# TMS1_2025_INVERTED.net
KiCad netlist of a schematic drawn in EasyEDA
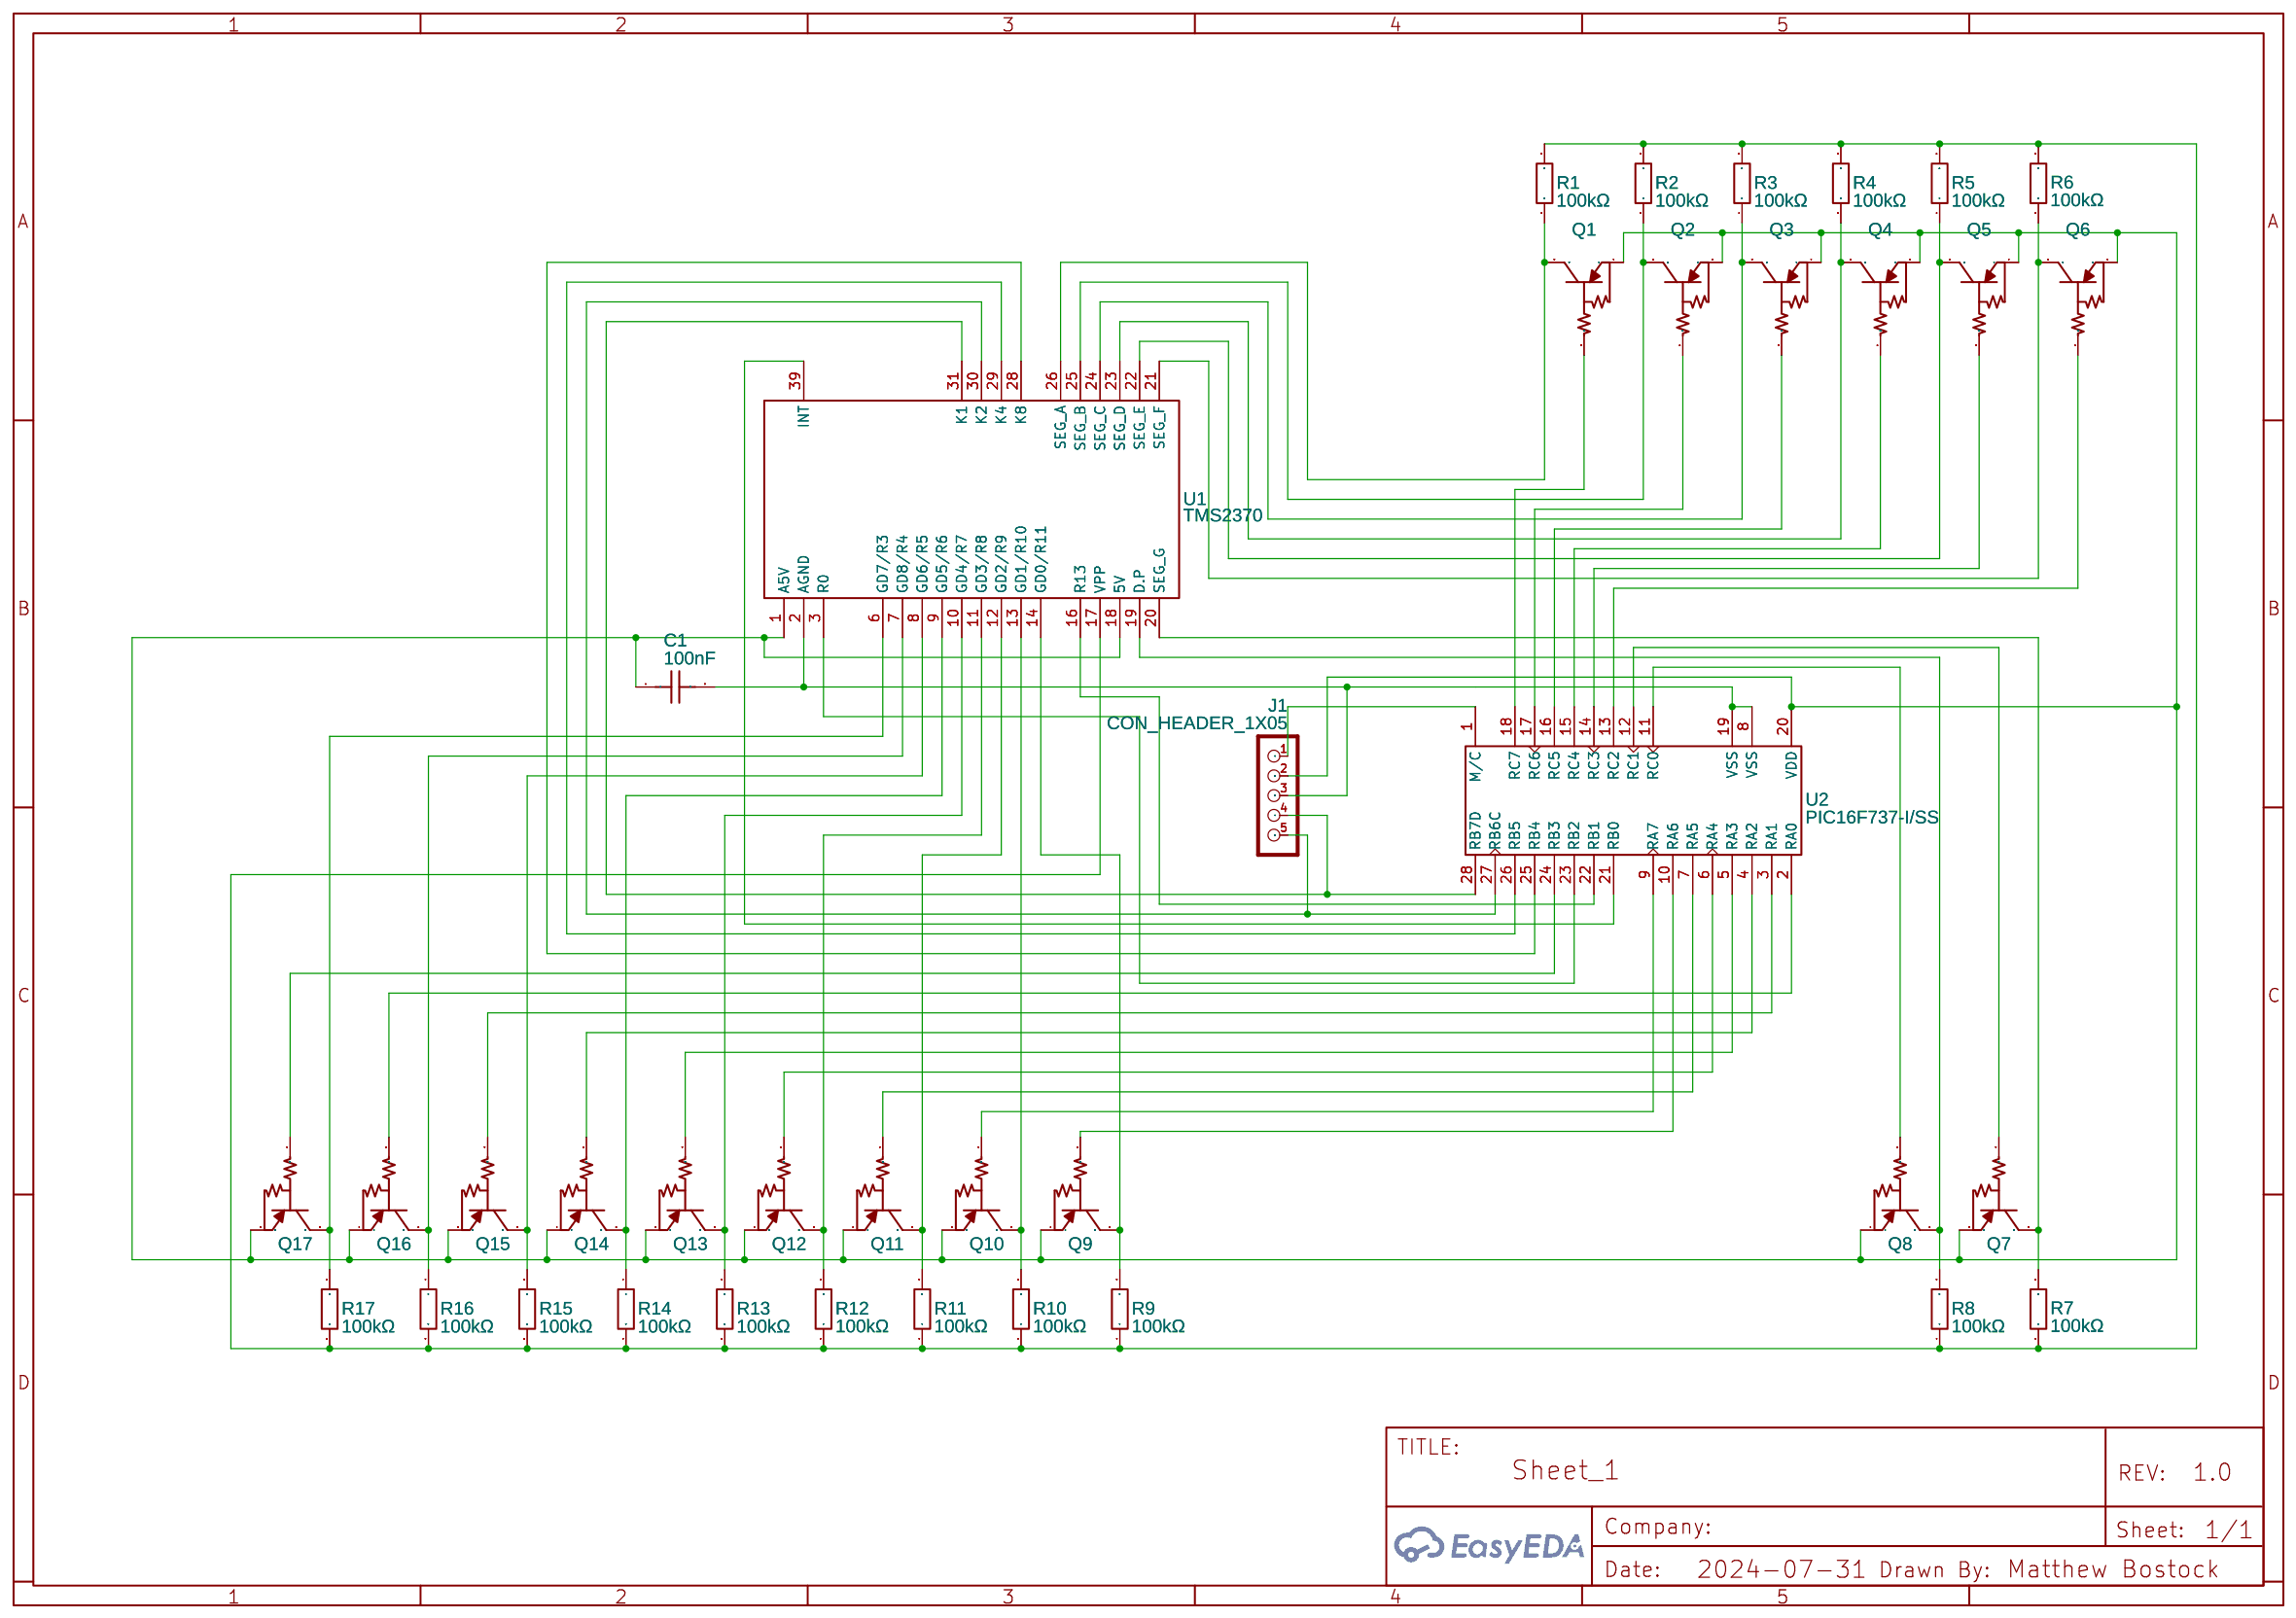
[diagram p0: schematic sheet]

(export (version "E")
  (design (tool "Eeschema 10.0.6"))
  (components
    (comp (ref "C1")
      (value "100nF")
      (fields
        (field (name "Manufacturer Part") "CC0603KRX7R9BB104")
        (field (name "Manufacturer") "YAGEO(国巨)")
      )
      (libsource (lib "") (part "CC0603KRX7R9BB104"))
    )
    (comp (ref "J1") (value "CON_HEADER_1X05") (libsource (lib "") (part "CON_HEADER_1X05")))
    (comp (ref "Q1")
      (value "DTB113ZKT146_SLIM")
      (fields (field (name "Manufacturer Part") "DTB113ZKT146") (field (name "Manufacturer") "ROHM(罗姆)"))
      (libsource (lib "") (part "DTB113ZKT146_SLIM_1"))
    )
    (comp (ref "Q2")
      (value "DTB113ZKT146_SLIM")
      (fields (field (name "Manufacturer Part") "DTB113ZKT146") (field (name "Manufacturer") "ROHM(罗姆)"))
      (libsource (lib "") (part "DTB113ZKT146_SLIM_1"))
    )
    (comp (ref "Q3")
      (value "DTB113ZKT146_SLIM")
      (fields (field (name "Manufacturer Part") "DTB113ZKT146") (field (name "Manufacturer") "ROHM(罗姆)"))
      (libsource (lib "") (part "DTB113ZKT146_SLIM_1"))
    )
    (comp (ref "Q4")
      (value "DTB113ZKT146_SLIM")
      (fields (field (name "Manufacturer Part") "DTB113ZKT146") (field (name "Manufacturer") "ROHM(罗姆)"))
      (libsource (lib "") (part "DTB113ZKT146_SLIM_1"))
    )
    (comp (ref "Q5")
      (value "DTB113ZKT146_SLIM")
      (fields (field (name "Manufacturer Part") "DTB113ZKT146") (field (name "Manufacturer") "ROHM(罗姆)"))
      (libsource (lib "") (part "DTB113ZKT146_SLIM_1"))
    )
    (comp (ref "Q6")
      (value "DTB113ZKT146_SLIM")
      (fields (field (name "Manufacturer Part") "DTB113ZKT146") (field (name "Manufacturer") "ROHM(罗姆)"))
      (libsource (lib "") (part "DTB113ZKT146_SLIM_1"))
    )
    (comp (ref "Q7")
      (value "DTB113ZKT146_SLIM")
      (fields (field (name "Manufacturer Part") "DTB113ZKT146") (field (name "Manufacturer") "ROHM(罗姆)"))
      (libsource (lib "") (part "DTB113ZKT146_SLIM"))
    )
    (comp (ref "Q8")
      (value "DTB113ZKT146_SLIM")
      (fields (field (name "Manufacturer Part") "DTB113ZKT146") (field (name "Manufacturer") "ROHM(罗姆)"))
      (libsource (lib "") (part "DTB113ZKT146_SLIM"))
    )
    (comp (ref "Q9")
      (value "DTB113ZKT146_SLIM")
      (fields (field (name "Manufacturer Part") "DTB113ZKT146") (field (name "Manufacturer") "ROHM(罗姆)"))
      (libsource (lib "") (part "DTB113ZKT146_SLIM"))
    )
    (comp (ref "Q10")
      (value "DTB113ZKT146_SLIM")
      (fields (field (name "Manufacturer Part") "DTB113ZKT146") (field (name "Manufacturer") "ROHM(罗姆)"))
      (libsource (lib "") (part "DTB113ZKT146_SLIM"))
    )
    (comp (ref "Q11")
      (value "DTB113ZKT146_SLIM")
      (fields (field (name "Manufacturer Part") "DTB113ZKT146") (field (name "Manufacturer") "ROHM(罗姆)"))
      (libsource (lib "") (part "DTB113ZKT146_SLIM"))
    )
    (comp (ref "Q12")
      (value "DTB113ZKT146_SLIM")
      (fields (field (name "Manufacturer Part") "DTB113ZKT146") (field (name "Manufacturer") "ROHM(罗姆)"))
      (libsource (lib "") (part "DTB113ZKT146_SLIM"))
    )
    (comp (ref "Q13")
      (value "DTB113ZKT146_SLIM")
      (fields (field (name "Manufacturer Part") "DTB113ZKT146") (field (name "Manufacturer") "ROHM(罗姆)"))
      (libsource (lib "") (part "DTB113ZKT146_SLIM"))
    )
    (comp (ref "Q14")
      (value "DTB113ZKT146_SLIM")
      (fields (field (name "Manufacturer Part") "DTB113ZKT146") (field (name "Manufacturer") "ROHM(罗姆)"))
      (libsource (lib "") (part "DTB113ZKT146_SLIM"))
    )
    (comp (ref "Q15")
      (value "DTB113ZKT146_SLIM")
      (fields (field (name "Manufacturer Part") "DTB113ZKT146") (field (name "Manufacturer") "ROHM(罗姆)"))
      (libsource (lib "") (part "DTB113ZKT146_SLIM"))
    )
    (comp (ref "Q16")
      (value "DTB113ZKT146_SLIM")
      (fields (field (name "Manufacturer Part") "DTB113ZKT146") (field (name "Manufacturer") "ROHM(罗姆)"))
      (libsource (lib "") (part "DTB113ZKT146_SLIM"))
    )
    (comp (ref "Q17")
      (value "DTB113ZKT146_SLIM")
      (fields (field (name "Manufacturer Part") "DTB113ZKT146") (field (name "Manufacturer") "ROHM(罗姆)"))
      (libsource (lib "") (part "DTB113ZKT146_SLIM"))
    )
    (comp (ref "R1")
      (value "100kΩ")
      (fields (field (name "Manufacturer Part") "RC0603FR-07100KL") (field (name "Manufacturer") "YAGEO(国巨)"))
      (libsource (lib "") (part "RC0603FR-07100KL"))
    )
    (comp (ref "R2")
      (value "100kΩ")
      (fields (field (name "Manufacturer Part") "RC0603FR-07100KL") (field (name "Manufacturer") "YAGEO(国巨)"))
      (libsource (lib "") (part "RC0603FR-07100KL"))
    )
    (comp (ref "R3")
      (value "100kΩ")
      (fields (field (name "Manufacturer Part") "RC0603FR-07100KL") (field (name "Manufacturer") "YAGEO(国巨)"))
      (libsource (lib "") (part "RC0603FR-07100KL"))
    )
    (comp (ref "R4")
      (value "100kΩ")
      (fields (field (name "Manufacturer Part") "RC0603FR-07100KL") (field (name "Manufacturer") "YAGEO(国巨)"))
      (libsource (lib "") (part "RC0603FR-07100KL"))
    )
    (comp (ref "R5")
      (value "100kΩ")
      (fields (field (name "Manufacturer Part") "RC0603FR-07100KL") (field (name "Manufacturer") "YAGEO(国巨)"))
      (libsource (lib "") (part "RC0603FR-07100KL"))
    )
    (comp (ref "R6")
      (value "100kΩ")
      (fields (field (name "Manufacturer Part") "RC0603FR-07100KL") (field (name "Manufacturer") "YAGEO(国巨)"))
      (libsource (lib "") (part "RC0603FR-07100KL"))
    )
    (comp (ref "R7")
      (value "100kΩ")
      (fields (field (name "Manufacturer Part") "RC0603FR-07100KL") (field (name "Manufacturer") "YAGEO(国巨)"))
      (libsource (lib "") (part "RC0603FR-07100KL"))
    )
    (comp (ref "R8")
      (value "100kΩ")
      (fields (field (name "Manufacturer Part") "RC0603FR-07100KL") (field (name "Manufacturer") "YAGEO(国巨)"))
      (libsource (lib "") (part "RC0603FR-07100KL"))
    )
    (comp (ref "R9")
      (value "100kΩ")
      (fields (field (name "Manufacturer Part") "RC0603FR-07100KL") (field (name "Manufacturer") "YAGEO(国巨)"))
      (libsource (lib "") (part "RC0603FR-07100KL"))
    )
    (comp (ref "R10")
      (value "100kΩ")
      (fields (field (name "Manufacturer Part") "RC0603FR-07100KL") (field (name "Manufacturer") "YAGEO(国巨)"))
      (libsource (lib "") (part "RC0603FR-07100KL"))
    )
    (comp (ref "R11")
      (value "100kΩ")
      (fields (field (name "Manufacturer Part") "RC0603FR-07100KL") (field (name "Manufacturer") "YAGEO(国巨)"))
      (libsource (lib "") (part "RC0603FR-07100KL"))
    )
    (comp (ref "R12")
      (value "100kΩ")
      (fields (field (name "Manufacturer Part") "RC0603FR-07100KL") (field (name "Manufacturer") "YAGEO(国巨)"))
      (libsource (lib "") (part "RC0603FR-07100KL"))
    )
    (comp (ref "R13")
      (value "100kΩ")
      (fields (field (name "Manufacturer Part") "RC0603FR-07100KL") (field (name "Manufacturer") "YAGEO(国巨)"))
      (libsource (lib "") (part "RC0603FR-07100KL_1"))
    )
    (comp (ref "R14")
      (value "100kΩ")
      (fields (field (name "Manufacturer Part") "RC0603FR-07100KL") (field (name "Manufacturer") "YAGEO(国巨)"))
      (libsource (lib "") (part "RC0603FR-07100KL_1"))
    )
    (comp (ref "R15")
      (value "100kΩ")
      (fields (field (name "Manufacturer Part") "RC0603FR-07100KL") (field (name "Manufacturer") "YAGEO(国巨)"))
      (libsource (lib "") (part "RC0603FR-07100KL_1"))
    )
    (comp (ref "R16")
      (value "100kΩ")
      (fields (field (name "Manufacturer Part") "RC0603FR-07100KL") (field (name "Manufacturer") "YAGEO(国巨)"))
      (libsource (lib "") (part "RC0603FR-07100KL_1"))
    )
    (comp (ref "R17")
      (value "100kΩ")
      (fields (field (name "Manufacturer Part") "RC0603FR-07100KL") (field (name "Manufacturer") "YAGEO(国巨)"))
      (libsource (lib "") (part "RC0603FR-07100KL_1"))
    )
    (comp (ref "U1")
      (value "TMS2370")
      (fields (field (name "Manufacturer") "Texas Instruments"))
      (libsource (lib "") (part "TMS2370"))
    )
    (comp (ref "U2")
      (value "PIC16F737-I/SS")
      (fields
        (field (name "Manufacturer Part") "PIC16F737-I/SO")
        (field (name "Manufacturer") "MICROCHIP(美国微芯)")
      )
      (libsource (lib "") (part "PIC16F737-I/SO_SLIM"))
    )
  )
  (nets
    (net (code "1") (name "Net-(Q1-B)") (class "Default")
      (node (ref "Q1") (pin "2") (pinfunction "B_2") (pintype "unspecified"))
      (node (ref "U2") (pin "18") (pinfunction "RC7_18") (pintype "unspecified"))
    )
    (net (code "2") (name "Net-(Q1-C)") (class "Default")
      (node (ref "Q1") (pin "3") (pinfunction "C_3") (pintype "unspecified"))
      (node (ref "R1") (pin "1") (pinfunction "1_1") (pintype "unspecified"))
      (node (ref "U1") (pin "26") (pinfunction "SEG_A_26") (pintype "unspecified"))
    )
    (net (code "3") (name "Net-(Q1-E)") (class "Default")
      (node (ref "C1") (pin "1") (pinfunction "1_1") (pintype "unspecified"))
      (node (ref "J1") (pin "2") (pinfunction "2_2") (pintype "unspecified"))
      (node (ref "Q1") (pin "1") (pinfunction "E_1") (pintype "unspecified"))
      (node (ref "Q10") (pin "1") (pinfunction "E_1") (pintype "unspecified"))
      (node (ref "Q11") (pin "1") (pinfunction "E_1") (pintype "unspecified"))
      (node (ref "Q12") (pin "1") (pinfunction "E_1") (pintype "unspecified"))
      (node (ref "Q13") (pin "1") (pinfunction "E_1") (pintype "unspecified"))
      (node (ref "Q14") (pin "1") (pinfunction "E_1") (pintype "unspecified"))
      (node (ref "Q15") (pin "1") (pinfunction "E_1") (pintype "unspecified"))
      (node (ref "Q16") (pin "1") (pinfunction "E_1") (pintype "unspecified"))
      (node (ref "Q17") (pin "1") (pinfunction "E_1") (pintype "unspecified"))
      (node (ref "Q2") (pin "1") (pinfunction "E_1") (pintype "unspecified"))
      (node (ref "Q3") (pin "1") (pinfunction "E_1") (pintype "unspecified"))
      (node (ref "Q4") (pin "1") (pinfunction "E_1") (pintype "unspecified"))
      (node (ref "Q5") (pin "1") (pinfunction "E_1") (pintype "unspecified"))
      (node (ref "Q6") (pin "1") (pinfunction "E_1") (pintype "unspecified"))
      (node (ref "Q7") (pin "1") (pinfunction "E_1") (pintype "unspecified"))
      (node (ref "Q8") (pin "1") (pinfunction "E_1") (pintype "unspecified"))
      (node (ref "Q9") (pin "1") (pinfunction "E_1") (pintype "unspecified"))
      (node (ref "U1") (pin "1") (pinfunction "A5V_1") (pintype "unspecified"))
      (node (ref "U1") (pin "18") (pinfunction "5V_18") (pintype "unspecified"))
      (node (ref "U2") (pin "20") (pinfunction "VDD_20") (pintype "unspecified"))
    )
    (net (code "4") (name "Net-(Q2-B)") (class "Default")
      (node (ref "Q2") (pin "2") (pinfunction "B_2") (pintype "unspecified"))
      (node (ref "U2") (pin "17") (pinfunction "RC6_17") (pintype "unspecified"))
    )
    (net (code "5") (name "Net-(Q2-C)") (class "Default")
      (node (ref "Q2") (pin "3") (pinfunction "C_3") (pintype "unspecified"))
      (node (ref "R2") (pin "1") (pinfunction "1_1") (pintype "unspecified"))
      (node (ref "U1") (pin "25") (pinfunction "SEG_B_25") (pintype "unspecified"))
    )
    (net (code "6") (name "Net-(Q3-B)") (class "Default")
      (node (ref "Q3") (pin "2") (pinfunction "B_2") (pintype "unspecified"))
      (node (ref "U2") (pin "16") (pinfunction "RC5_16") (pintype "unspecified"))
    )
    (net (code "7") (name "Net-(Q3-C)") (class "Default")
      (node (ref "Q3") (pin "3") (pinfunction "C_3") (pintype "unspecified"))
      (node (ref "R3") (pin "1") (pinfunction "1_1") (pintype "unspecified"))
      (node (ref "U1") (pin "24") (pinfunction "SEG_C_24") (pintype "unspecified"))
    )
    (net (code "8") (name "Net-(Q4-B)") (class "Default")
      (node (ref "Q4") (pin "2") (pinfunction "B_2") (pintype "unspecified"))
      (node (ref "U2") (pin "15") (pinfunction "RC4_15") (pintype "unspecified"))
    )
    (net (code "9") (name "Net-(Q4-C)") (class "Default")
      (node (ref "Q4") (pin "3") (pinfunction "C_3") (pintype "unspecified"))
      (node (ref "R4") (pin "1") (pinfunction "1_1") (pintype "unspecified"))
      (node (ref "U1") (pin "23") (pinfunction "SEG_D_23") (pintype "unspecified"))
    )
    (net (code "10") (name "Net-(Q5-B)") (class "Default")
      (node (ref "Q5") (pin "2") (pinfunction "B_2") (pintype "unspecified"))
      (node (ref "U2") (pin "14") (pinfunction "RC3_14") (pintype "unspecified"))
    )
    (net (code "11") (name "Net-(Q5-C)") (class "Default")
      (node (ref "Q5") (pin "3") (pinfunction "C_3") (pintype "unspecified"))
      (node (ref "R5") (pin "1") (pinfunction "1_1") (pintype "unspecified"))
      (node (ref "U1") (pin "22") (pinfunction "SEG_E_22") (pintype "unspecified"))
    )
    (net (code "12") (name "Net-(Q6-B)") (class "Default")
      (node (ref "Q6") (pin "2") (pinfunction "B_2") (pintype "unspecified"))
      (node (ref "U2") (pin "13") (pinfunction "RC2_13") (pintype "unspecified"))
    )
    (net (code "13") (name "Net-(Q6-C)") (class "Default")
      (node (ref "Q6") (pin "3") (pinfunction "C_3") (pintype "unspecified"))
      (node (ref "R6") (pin "1") (pinfunction "1_1") (pintype "unspecified"))
      (node (ref "U1") (pin "21") (pinfunction "SEG_F_21") (pintype "unspecified"))
    )
    (net (code "14") (name "Net-(Q7-B)") (class "Default")
      (node (ref "Q7") (pin "2") (pinfunction "B_2") (pintype "unspecified"))
      (node (ref "U2") (pin "12") (pinfunction "RC1_12") (pintype "unspecified"))
    )
    (net (code "15") (name "Net-(Q7-C)") (class "Default")
      (node (ref "Q7") (pin "3") (pinfunction "C_3") (pintype "unspecified"))
      (node (ref "R7") (pin "2") (pinfunction "2_2") (pintype "unspecified"))
      (node (ref "U1") (pin "20") (pinfunction "SEG_G_20") (pintype "unspecified"))
    )
    (net (code "16") (name "Net-(Q8-B)") (class "Default")
      (node (ref "Q8") (pin "2") (pinfunction "B_2") (pintype "unspecified"))
      (node (ref "U2") (pin "11") (pinfunction "RC0_11") (pintype "unspecified"))
    )
    (net (code "17") (name "Net-(Q8-C)") (class "Default")
      (node (ref "Q8") (pin "3") (pinfunction "C_3") (pintype "unspecified"))
      (node (ref "R8") (pin "2") (pinfunction "2_2") (pintype "unspecified"))
      (node (ref "U1") (pin "19") (pinfunction "D.P_19") (pintype "unspecified"))
    )
    (net (code "18") (name "Net-(Q9-B)") (class "Default")
      (node (ref "Q9") (pin "2") (pinfunction "B_2") (pintype "unspecified"))
      (node (ref "U2") (pin "10") (pinfunction "RA6_10") (pintype "unspecified"))
    )
    (net (code "19") (name "Net-(Q9-C)") (class "Default")
      (node (ref "Q9") (pin "3") (pinfunction "C_3") (pintype "unspecified"))
      (node (ref "R9") (pin "2") (pinfunction "2_2") (pintype "unspecified"))
      (node (ref "U1") (pin "14") (pinfunction "GD0/R11_14") (pintype "unspecified"))
    )
    (net (code "20") (name "Net-(Q10-B)") (class "Default")
      (node (ref "Q10") (pin "2") (pinfunction "B_2") (pintype "unspecified"))
      (node (ref "U2") (pin "9") (pinfunction "RA7_9") (pintype "unspecified"))
    )
    (net (code "21") (name "Net-(Q10-C)") (class "Default")
      (node (ref "Q10") (pin "3") (pinfunction "C_3") (pintype "unspecified"))
      (node (ref "R10") (pin "2") (pinfunction "2_2") (pintype "unspecified"))
      (node (ref "U1") (pin "13") (pinfunction "GD1/R10_13") (pintype "unspecified"))
    )
    (net (code "22") (name "Net-(Q11-B)") (class "Default")
      (node (ref "Q11") (pin "2") (pinfunction "B_2") (pintype "unspecified"))
      (node (ref "U2") (pin "7") (pinfunction "RA5_7") (pintype "unspecified"))
    )
    (net (code "23") (name "Net-(Q11-C)") (class "Default")
      (node (ref "Q11") (pin "3") (pinfunction "C_3") (pintype "unspecified"))
      (node (ref "R11") (pin "2") (pinfunction "2_2") (pintype "unspecified"))
      (node (ref "U1") (pin "12") (pinfunction "GD2/R9_12") (pintype "unspecified"))
    )
    (net (code "24") (name "Net-(Q12-B)") (class "Default")
      (node (ref "Q12") (pin "2") (pinfunction "B_2") (pintype "unspecified"))
      (node (ref "U2") (pin "6") (pinfunction "RA4_6") (pintype "unspecified"))
    )
    (net (code "25") (name "Net-(Q12-C)") (class "Default")
      (node (ref "Q12") (pin "3") (pinfunction "C_3") (pintype "unspecified"))
      (node (ref "R12") (pin "2") (pinfunction "2_2") (pintype "unspecified"))
      (node (ref "U1") (pin "11") (pinfunction "GD3/R8_11") (pintype "unspecified"))
    )
    (net (code "26") (name "Net-(Q13-B)") (class "Default")
      (node (ref "Q13") (pin "2") (pinfunction "B_2") (pintype "unspecified"))
      (node (ref "U2") (pin "5") (pinfunction "RA3_5") (pintype "unspecified"))
    )
    (net (code "27") (name "Net-(Q13-C)") (class "Default")
      (node (ref "Q13") (pin "3") (pinfunction "C_3") (pintype "unspecified"))
      (node (ref "R13") (pin "1") (pinfunction "1_1") (pintype "unspecified"))
      (node (ref "U1") (pin "10") (pinfunction "GD4/R7_10") (pintype "unspecified"))
    )
    (net (code "28") (name "Net-(Q14-B)") (class "Default")
      (node (ref "Q14") (pin "2") (pinfunction "B_2") (pintype "unspecified"))
      (node (ref "U2") (pin "4") (pinfunction "RA2_4") (pintype "unspecified"))
    )
    (net (code "29") (name "Net-(Q14-C)") (class "Default")
      (node (ref "Q14") (pin "3") (pinfunction "C_3") (pintype "unspecified"))
      (node (ref "R14") (pin "1") (pinfunction "1_1") (pintype "unspecified"))
      (node (ref "U1") (pin "9") (pinfunction "GD5/R6_9") (pintype "unspecified"))
    )
    (net (code "30") (name "Net-(Q15-B)") (class "Default")
      (node (ref "Q15") (pin "2") (pinfunction "B_2") (pintype "unspecified"))
      (node (ref "U2") (pin "3") (pinfunction "RA1_3") (pintype "unspecified"))
    )
    (net (code "31") (name "Net-(Q15-C)") (class "Default")
      (node (ref "Q15") (pin "3") (pinfunction "C_3") (pintype "unspecified"))
      (node (ref "R15") (pin "1") (pinfunction "1_1") (pintype "unspecified"))
      (node (ref "U1") (pin "8") (pinfunction "GD6/R5_8") (pintype "unspecified"))
    )
    (net (code "32") (name "Net-(Q16-B)") (class "Default")
      (node (ref "Q16") (pin "2") (pinfunction "B_2") (pintype "unspecified"))
      (node (ref "U2") (pin "2") (pinfunction "RA0_2") (pintype "unspecified"))
    )
    (net (code "33") (name "Net-(Q16-C)") (class "Default")
      (node (ref "Q16") (pin "3") (pinfunction "C_3") (pintype "unspecified"))
      (node (ref "R16") (pin "1") (pinfunction "1_1") (pintype "unspecified"))
      (node (ref "U1") (pin "7") (pinfunction "GD8/R4_7") (pintype "unspecified"))
    )
    (net (code "34") (name "Net-(Q17-B)") (class "Default")
      (node (ref "Q17") (pin "2") (pinfunction "B_2") (pintype "unspecified"))
      (node (ref "U2") (pin "24") (pinfunction "RB3_24") (pintype "unspecified"))
    )
    (net (code "35") (name "Net-(Q17-C)") (class "Default")
      (node (ref "Q17") (pin "3") (pinfunction "C_3") (pintype "unspecified"))
      (node (ref "R17") (pin "1") (pinfunction "1_1") (pintype "unspecified"))
      (node (ref "U1") (pin "6") (pinfunction "GD7/R3_6") (pintype "unspecified"))
    )
    (net (code "36") (name "Net-(U1-AGND)") (class "Default")
      (node (ref "C1") (pin "2") (pinfunction "2_2") (pintype "unspecified"))
      (node (ref "J1") (pin "3") (pinfunction "3_3") (pintype "unspecified"))
      (node (ref "U1") (pin "2") (pinfunction "AGND_2") (pintype "unspecified"))
      (node (ref "U2") (pin "19") (pinfunction "VSS_19") (pintype "unspecified"))
      (node (ref "U2") (pin "8") (pinfunction "VSS_8") (pintype "unspecified"))
    )
    (net (code "37") (name "Net-(U1-INT)") (class "Default")
      (node (ref "U1") (pin "39") (pinfunction "INT_39") (pintype "unspecified"))
      (node (ref "U2") (pin "21") (pinfunction "RB0_21") (pintype "unspecified"))
    )
    (net (code "38") (name "Net-(U1-K1)") (class "Default")
      (node (ref "J1") (pin "4") (pinfunction "4_4") (pintype "unspecified"))
      (node (ref "U1") (pin "31") (pinfunction "K1_31") (pintype "unspecified"))
      (node (ref "U2") (pin "28") (pinfunction "RB7D_28") (pintype "unspecified"))
    )
    (net (code "39") (name "Net-(U1-K2)") (class "Default")
      (node (ref "J1") (pin "5") (pinfunction "5_5") (pintype "unspecified"))
      (node (ref "U1") (pin "30") (pinfunction "K2_30") (pintype "unspecified"))
      (node (ref "U2") (pin "27") (pinfunction "RB6C_27") (pintype "unspecified"))
    )
    (net (code "40") (name "Net-(U1-K4)") (class "Default")
      (node (ref "U1") (pin "29") (pinfunction "K4_29") (pintype "unspecified"))
      (node (ref "U2") (pin "26") (pinfunction "RB5_26") (pintype "unspecified"))
    )
    (net (code "41") (name "Net-(U1-K8)") (class "Default")
      (node (ref "U1") (pin "28") (pinfunction "K8_28") (pintype "unspecified"))
      (node (ref "U2") (pin "25") (pinfunction "RB4_25") (pintype "unspecified"))
    )
    (net (code "42") (name "Net-(U1-R0)") (class "Default")
      (node (ref "U1") (pin "3") (pinfunction "R0_3") (pintype "unspecified"))
      (node (ref "U2") (pin "23") (pinfunction "RB2_23") (pintype "unspecified"))
    )
    (net (code "43") (name "Net-(U1-R13)") (class "Default")
      (node (ref "U1") (pin "16") (pinfunction "R13_16") (pintype "unspecified"))
      (node (ref "U2") (pin "22") (pinfunction "RB1_22") (pintype "unspecified"))
    )
    (net (code "44") (name "Net-(U1-VPP)") (class "Default")
      (node (ref "R1") (pin "2") (pinfunction "2_2") (pintype "unspecified"))
      (node (ref "R10") (pin "1") (pinfunction "1_1") (pintype "unspecified"))
      (node (ref "R11") (pin "1") (pinfunction "1_1") (pintype "unspecified"))
      (node (ref "R12") (pin "1") (pinfunction "1_1") (pintype "unspecified"))
      (node (ref "R13") (pin "2") (pinfunction "2_2") (pintype "unspecified"))
      (node (ref "R14") (pin "2") (pinfunction "2_2") (pintype "unspecified"))
      (node (ref "R15") (pin "2") (pinfunction "2_2") (pintype "unspecified"))
      (node (ref "R16") (pin "2") (pinfunction "2_2") (pintype "unspecified"))
      (node (ref "R17") (pin "2") (pinfunction "2_2") (pintype "unspecified"))
      (node (ref "R2") (pin "2") (pinfunction "2_2") (pintype "unspecified"))
      (node (ref "R3") (pin "2") (pinfunction "2_2") (pintype "unspecified"))
      (node (ref "R4") (pin "2") (pinfunction "2_2") (pintype "unspecified"))
      (node (ref "R5") (pin "2") (pinfunction "2_2") (pintype "unspecified"))
      (node (ref "R6") (pin "2") (pinfunction "2_2") (pintype "unspecified"))
      (node (ref "R7") (pin "1") (pinfunction "1_1") (pintype "unspecified"))
      (node (ref "R8") (pin "1") (pinfunction "1_1") (pintype "unspecified"))
      (node (ref "R9") (pin "1") (pinfunction "1_1") (pintype "unspecified"))
      (node (ref "U1") (pin "17") (pinfunction "VPP_17") (pintype "unspecified"))
    )
    (net (code "45") (name "Net-(U2-M{slash}C)") (class "Default")
      (node (ref "J1") (pin "1") (pinfunction "1_1") (pintype "unspecified"))
      (node (ref "U2") (pin "1") (pinfunction "M/C_1") (pintype "unspecified"))
    )
  )
)
